# current_sensor_hall.net
KiCad netlist of a schematic drawn in Altium Designer
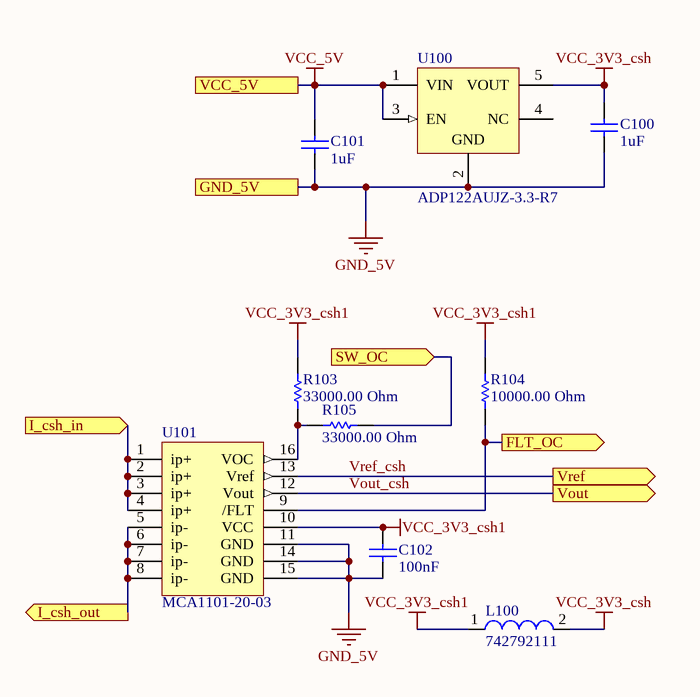
[diagram p0: current_sensor_hall.SchDoc]

(export (version "E")
  (design (tool "Eeschema 10.0.6"))
  (components
    (comp (ref "C100")
      (value "1uF")
      (footprint "CAPC0603(1608)100_N")
      (description "CAP 1uF 50V ±20% 0603 (1608 Metric) Thickness 1mm SMD")
      (fields (field (name "TOLERANCE") "Â±20%") (field (name "Comment") "CAP 1uF 50V 0603(1608)"))
      (libsource (lib "Altium Content Vault") (part "CAP"))
    )
    (comp (ref "C101")
      (value "1uF")
      (footprint "CAPC0603(1608)100_N")
      (description "CAP 1uF 50V ±20% 0603 (1608 Metric) Thickness 1mm SMD")
      (fields (field (name "TOLERANCE") "Â±20%") (field (name "Comment") "CAP 1uF 50V 0603(1608)"))
      (libsource (lib "Altium Content Vault") (part "CAP"))
    )
    (comp (ref "C102")
      (value "100nF")
      (footprint "CAPC0603(1608)100_L")
      (description "CAP 100nF 10V ±10% 0603 (1608 Metric) Thickness 1mm SMD")
      (fields (field (name "TOLERANCE") "Â±10%") (field (name "Comment") "CAP 100nF 10V 0603(1608)"))
      (libsource (lib "Altium Content Vault") (part "CAP"))
    )
    (comp (ref "L100")
      (value "742792111")
      (footprint "SMD-1206")
      (description "SMD EMI Suppression Ferrite Bead WE-CBF, Z = 26 Ohm")
      (libsource (lib "Altium Content Vault") (part "PAS-IND-INDUCTOR-2"))
    )
    (comp (ref "R103")
      (value "33000.00 Ohm")
      (footprint "RESC0805(2012)_L")
      (description "33K 0.125W 5% 0805 (2012 Metric)  SMD")
      (fields (field (name "POWER") "0.125 W") (field (name "TOLERANCE") "5 %"))
      (libsource (lib "Altium Content Vault") (part "RES"))
    )
    (comp (ref "R104")
      (value "10000.00 Ohm")
      (footprint "RESC0603(1608)_L")
      (description "10K 0.1W 5% 0603 (1608 Metric)  SMD")
      (fields (field (name "TOLERANCE") "5 %") (field (name "POWER") "0.1 W"))
      (libsource (lib "Altium Content Vault") (part "RES"))
    )
    (comp (ref "R105")
      (value "33000.00 Ohm")
      (footprint "RESC0805(2012)_L")
      (description "33K 0.125W 5% 0805 (2012 Metric)  SMD")
      (fields (field (name "POWER") "0.125 W") (field (name "TOLERANCE") "5 %"))
      (libsource (lib "Altium Content Vault") (part "RES"))
    )
    (comp (ref "U100")
      (value "ADP122AUJZ-3.3-R7")
      (footprint "ADI-UJ-5_L")
      (fields (field (name "MANUFACTURER") "Analog Devices"))
      (libsource (lib "Altium Content Vault") (part "ADI-ADP1XX-UJ-5"))
    )
    (comp (ref "U101")
      (value "MCA1101-20-03")
      (footprint "SOIC127P1030X265-16N")
      (description "High Accuracy Current Sensor IC with 1.5MHz 3dB Bandwidth and Isolation ±20A,, 3.3V, Ratiometric")
      (fields (field (name "MANUFACTURER") "ACEINNA") (field (name "MOUSER PART NUMBER") "438-MCA1101-20-3"))
      (libsource (lib "Altium_Library_POWERLAB") (part "MCA1101-20-03"))
    )
  )
  (nets
    (net (code "1") (name "/FLT_OC") (class "Default")
      (node (ref "R104") (pin "2") (pinfunction "2_2") (pintype "passive"))
      (node (ref "U101") (pin "9") (pinfunction "/FLT_9") (pintype "open_collector"))
    )
    (net (code "2") (name "/I_csh_in") (class "Default")
      (node (ref "U101") (pin "1") (pinfunction "ip+_1") (pintype "passive"))
      (node (ref "U101") (pin "2") (pinfunction "ip+_2") (pintype "passive"))
      (node (ref "U101") (pin "3") (pinfunction "ip+_3") (pintype "passive"))
      (node (ref "U101") (pin "4") (pinfunction "ip+_4") (pintype "passive"))
    )
    (net (code "3") (name "/I_csh_out") (class "Default")
      (node (ref "U101") (pin "5") (pinfunction "ip-_5") (pintype "passive"))
      (node (ref "U101") (pin "6") (pinfunction "ip-_6") (pintype "passive"))
      (node (ref "U101") (pin "7") (pinfunction "ip-_7") (pintype "passive"))
      (node (ref "U101") (pin "8") (pinfunction "ip-_8") (pintype "passive"))
    )
    (net (code "4") (name "/SW_OC") (class "Default")
      (node (ref "R105") (pin "1") (pinfunction "1_1") (pintype "passive"))
    )
    (net (code "5") (name "/Vout_csh") (class "Default")
      (node (ref "U101") (pin "12") (pinfunction "Vout_12") (pintype "output"))
    )
    (net (code "6") (name "/Vref_csh") (class "Default")
      (node (ref "U101") (pin "13") (pinfunction "Vref_13") (pintype "output"))
    )
    (net (code "7") (name "GND_5V") (class "Default")
      (node (ref "C100") (pin "1") (pinfunction "1_1") (pintype "passive"))
      (node (ref "C101") (pin "1") (pinfunction "1_1") (pintype "passive"))
      (node (ref "C102") (pin "1") (pinfunction "1_1") (pintype "passive"))
      (node (ref "U100") (pin "2") (pinfunction "GND_2") (pintype "power_in"))
      (node (ref "U101") (pin "11") (pinfunction "GND_11") (pintype "power_in"))
      (node (ref "U101") (pin "14") (pinfunction "GND_14") (pintype "power_in"))
      (node (ref "U101") (pin "15") (pinfunction "GND_15") (pintype "power_in"))
    )
    (net (code "8") (name "Net-(U101-VOC)") (class "Default")
      (node (ref "R103") (pin "1") (pinfunction "1_1") (pintype "passive"))
      (node (ref "R105") (pin "2") (pinfunction "2_2") (pintype "passive"))
      (node (ref "U101") (pin "16") (pinfunction "VOC_16") (pintype "output"))
    )
    (net (code "9") (name "VCC_3V3_csh") (class "Default")
      (node (ref "C100") (pin "2") (pinfunction "2_2") (pintype "passive"))
      (node (ref "L100") (pin "2") (pinfunction "2_2") (pintype "passive"))
      (node (ref "U100") (pin "5") (pinfunction "VOUT_5") (pintype "power_in"))
    )
    (net (code "10") (name "VCC_3V3_csh1") (class "Default")
      (node (ref "C102") (pin "2") (pinfunction "2_2") (pintype "passive"))
      (node (ref "L100") (pin "1") (pinfunction "1_1") (pintype "passive"))
      (node (ref "R103") (pin "2") (pinfunction "2_2") (pintype "passive"))
      (node (ref "R104") (pin "1") (pinfunction "1_1") (pintype "passive"))
      (node (ref "U101") (pin "10") (pinfunction "VCC_10") (pintype "power_in"))
    )
    (net (code "11") (name "VCC_5V") (class "Default")
      (node (ref "C101") (pin "2") (pinfunction "2_2") (pintype "passive"))
      (node (ref "U100") (pin "1") (pinfunction "VIN_1") (pintype "power_in"))
      (node (ref "U100") (pin "3") (pinfunction "EN_3") (pintype "input"))
    )
    (net (code "12") (name "unconnected-(U100-NC-Pad4)") (class "Default")
      (node (ref "U100") (pin "4") (pinfunction "NC_4") (pintype "passive"))
    )
  )
)
